# simplePDschematicsv2_AZ_SMD.net
KiCad netlist of a schematic drawn in EAGLE
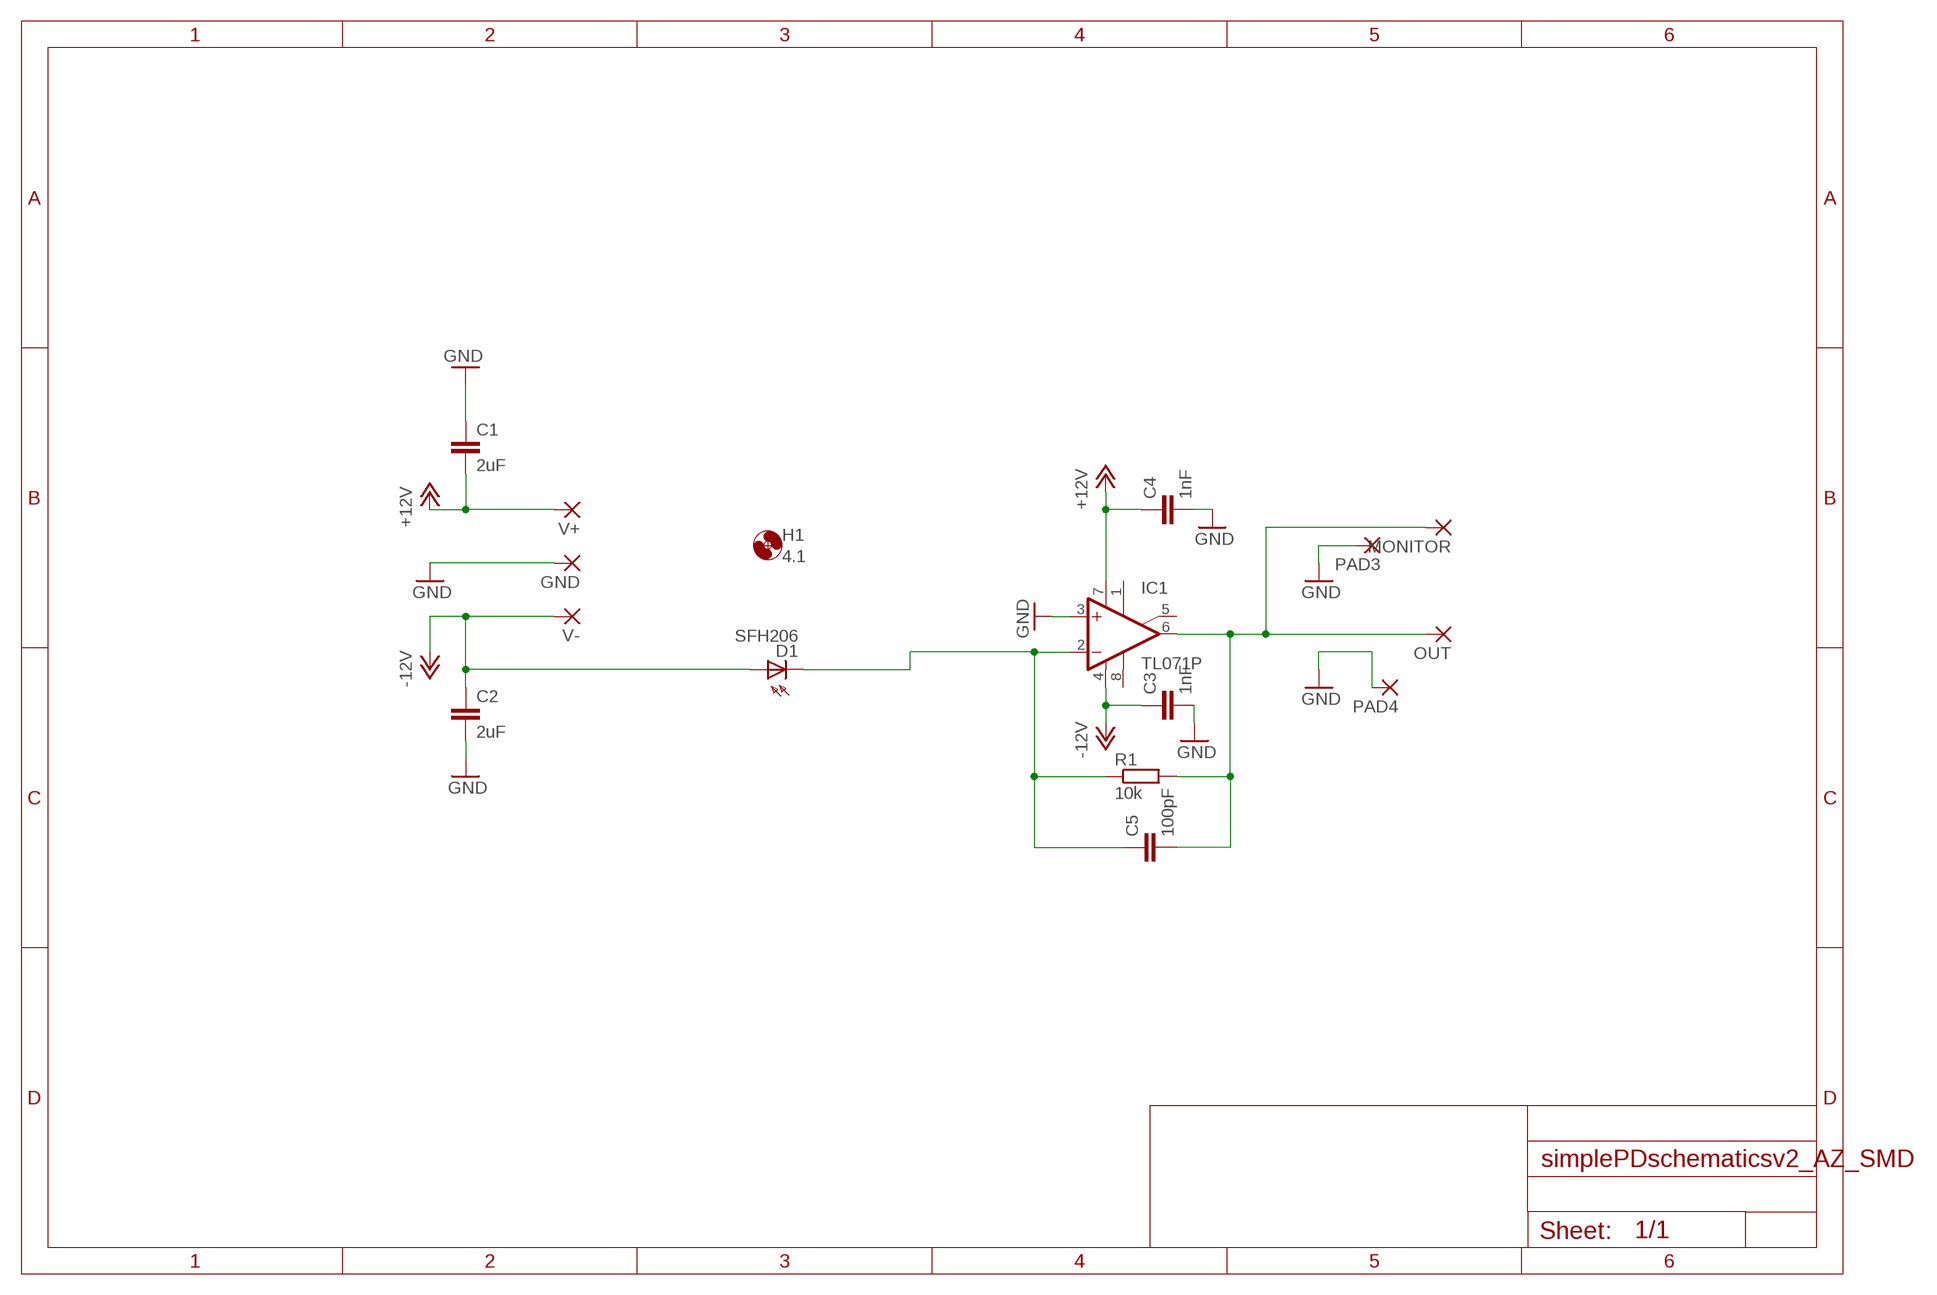
[diagram p0: schematic, sheet 1]

(export (version "E")
  (design (tool "Eeschema 10.0.6"))
  (components
    (comp (ref "C1")
      (value "2uF")
      (footprint "eagle-import:C050-075X075")
      (libsource (lib "eagle-import") (part "C-EU050-075X075"))
    )
    (comp (ref "C2")
      (value "2uF")
      (footprint "eagle-import:C050-075X075")
      (libsource (lib "eagle-import") (part "C-EU050-075X075"))
    )
    (comp (ref "C3")
      (value "1nF")
      (footprint "eagle-import:C025-050X050")
      (libsource (lib "eagle-import") (part "C-EU025-050X050"))
    )
    (comp (ref "C4")
      (value "1nF")
      (footprint "eagle-import:C025-050X050")
      (libsource (lib "eagle-import") (part "C-EU025-050X050"))
    )
    (comp (ref "C5")
      (value "100pF")
      (footprint "eagle-import:C025-050X050")
      (libsource (lib "eagle-import") (part "C-EU025-050X050"))
    )
    (comp (ref "D1")
      (value "SFH206")
      (footprint "eagle-import:SFH206")
      (fields (field (name "MPN") "SFH206K"))
      (libsource (lib "eagle-import") (part "SFH206"))
    )
    (comp (ref "GND")
      (value "1,6/0,9")
      (footprint "eagle-import:1,6_0,9")
      (libsource (lib "eagle-import") (part "1,6/0,9"))
    )
    (comp (ref "H1")
      (value "4.1")
      (footprint "eagle-import:4,1")
      (libsource (lib "eagle-import") (part "MOUNT-HOLE4.1"))
    )
    (comp (ref "IC1")
      (value "TL071P")
      (footprint "eagle-import:DIL08")
      (libsource (lib "eagle-import") (part "TL071P"))
    )
    (comp (ref "MONITOR")
      (value "1,6/0,9")
      (footprint "eagle-import:1,6_0,9")
      (libsource (lib "eagle-import") (part "1,6/0,9"))
    )
    (comp (ref "OUT")
      (value "1,6/0,9")
      (footprint "eagle-import:1,6_0,9")
      (libsource (lib "eagle-import") (part "1,6/0,9"))
    )
    (comp (ref "PAD3")
      (value "1,6/0,9")
      (footprint "eagle-import:1,6_0,9")
      (libsource (lib "eagle-import") (part "1,6/0,9"))
    )
    (comp (ref "PAD4")
      (value "1,6/0,9")
      (footprint "eagle-import:1,6_0,9")
      (libsource (lib "eagle-import") (part "1,6/0,9"))
    )
    (comp (ref "R1")
      (value "10k")
      (footprint "eagle-import:M1206")
      (libsource (lib "eagle-import") (part "R-EU_M1206"))
    )
    (comp (ref "V+")
      (value "1,6/0,9")
      (footprint "eagle-import:1,6_0,9")
      (libsource (lib "eagle-import") (part "1,6/0,9"))
    )
    (comp (ref "V-")
      (value "1,6/0,9")
      (footprint "eagle-import:1,6_0,9")
      (libsource (lib "eagle-import") (part "1,6/0,9"))
    )
  )
  (nets
    (net (code "1") (name "+12V") (class "Default")
      (node (ref "C1") (pin "2") (pinfunction "2_2") (pintype "passive"))
      (node (ref "C4") (pin "1") (pinfunction "1_1") (pintype "passive"))
      (node (ref "IC1") (pin "7") (pinfunction "V+_7") (pintype "power_in"))
      (node (ref "V+") (pin "1") (pinfunction "P_1") (pintype "passive"))
    )
    (net (code "2") (name "-12V") (class "Default")
      (node (ref "C2") (pin "1") (pinfunction "1_1") (pintype "passive"))
      (node (ref "C3") (pin "1") (pinfunction "1_1") (pintype "passive"))
      (node (ref "D1") (pin "A") (pinfunction "A_A") (pintype "passive"))
      (node (ref "IC1") (pin "4") (pinfunction "V-_4") (pintype "power_in"))
      (node (ref "V-") (pin "1") (pinfunction "P_1") (pintype "passive"))
    )
    (net (code "3") (name "GND") (class "Default")
      (node (ref "C1") (pin "1") (pinfunction "1_1") (pintype "passive"))
      (node (ref "C2") (pin "2") (pinfunction "2_2") (pintype "passive"))
      (node (ref "C3") (pin "2") (pinfunction "2_2") (pintype "passive"))
      (node (ref "C4") (pin "2") (pinfunction "2_2") (pintype "passive"))
      (node (ref "GND") (pin "1") (pinfunction "P_1") (pintype "passive"))
      (node (ref "IC1") (pin "3") (pinfunction "+IN_3") (pintype "input"))
      (node (ref "PAD3") (pin "1") (pinfunction "P_1") (pintype "passive"))
      (node (ref "PAD4") (pin "1") (pinfunction "P_1") (pintype "passive"))
    )
    (net (code "4") (name "Net-(D1-C)") (class "Default")
      (node (ref "C5") (pin "1") (pinfunction "1_1") (pintype "passive"))
      (node (ref "D1") (pin "K") (pinfunction "C_K") (pintype "passive"))
      (node (ref "IC1") (pin "2") (pinfunction "-IN_2") (pintype "input"))
      (node (ref "R1") (pin "1") (pinfunction "1_1") (pintype "passive"))
    )
    (net (code "5") (name "Net-(IC1-OUT)") (class "Default")
      (node (ref "C5") (pin "2") (pinfunction "2_2") (pintype "passive"))
      (node (ref "IC1") (pin "6") (pinfunction "OUT_6") (pintype "output"))
      (node (ref "MONITOR") (pin "1") (pinfunction "P_1") (pintype "passive"))
      (node (ref "OUT") (pin "1") (pinfunction "P_1") (pintype "passive"))
      (node (ref "R1") (pin "2") (pinfunction "2_2") (pintype "passive"))
    )
    (net (code "6") (name "unconnected-(IC1-ON1-Pad1)") (class "Default")
      (node (ref "IC1") (pin "1") (pinfunction "ON1_1") (pintype "passive"))
    )
    (net (code "7") (name "unconnected-(IC1-ON2-Pad5)") (class "Default")
      (node (ref "IC1") (pin "5") (pinfunction "ON2_5") (pintype "passive"))
    )
    (net (code "8") (name "unconnected-(IC1-OPT-Pad8)") (class "Default")
      (node (ref "IC1") (pin "8") (pinfunction "OPT_8") (pintype "passive"))
    )
  )
)
